# Status_LED.net
KiCad netlist of a schematic drawn in Altium Designer
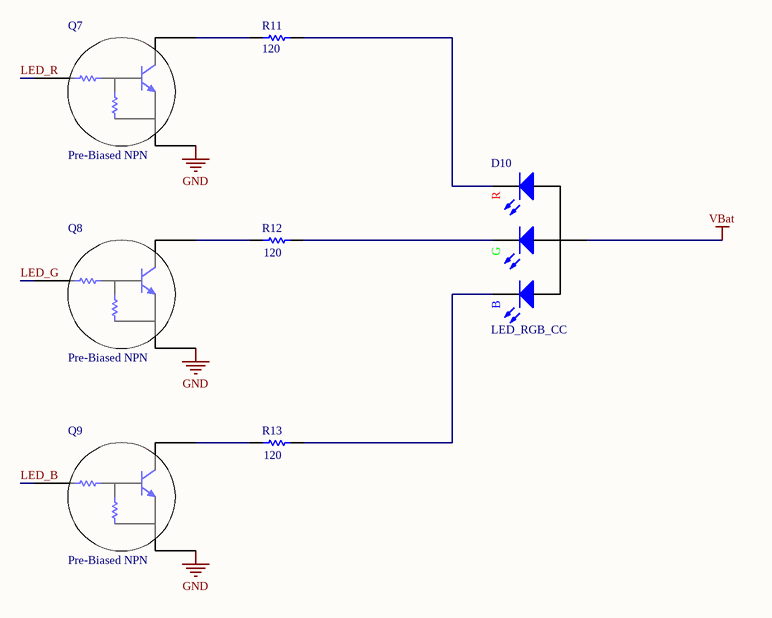
[diagram p0: Status_LED.SchDoc]

(export (version "E")
  (design (tool "Eeschema 10.0.6"))
  (components
    (comp (ref "D10")
      (value "LED_RGB_CC")
      (footprint "SM1210RGB")
      (description "RGB LED Common Cathode")
      (libsource (lib "passives") (part "LED_RGB_CC"))
    )
    (comp (ref "Q7")
      (value "Pre-Biased NPN")
      (footprint "SOT-416")
      (fields
        (field (name "MANUFACTURER PART NO") "DTD743EETL")
        (field (name "VENDOR PART NO") "DTD743EETLTR-ND")
      )
      (libsource (lib "transistors") (part "Pre-Biased NPN"))
    )
    (comp (ref "Q8")
      (value "Pre-Biased NPN")
      (footprint "SOT-416")
      (fields
        (field (name "MANUFACTURER PART NO") "DTD743EETL")
        (field (name "VENDOR PART NO") "DTD743EETLTR-ND")
      )
      (libsource (lib "transistors") (part "Pre-Biased NPN"))
    )
    (comp (ref "Q9")
      (value "Pre-Biased NPN")
      (footprint "SOT-416")
      (fields
        (field (name "MANUFACTURER PART NO") "DTD743EETL")
        (field (name "VENDOR PART NO") "DTD743EETLTR-ND")
      )
      (libsource (lib "transistors") (part "Pre-Biased NPN"))
    )
    (comp (ref "R11")
      (value "120")
      (footprint "0603")
      (description "Resistor")
      (fields (field (name "PUBLISHER") "Altium Limited"))
      (libsource (lib "passives") (part "Resistor"))
    )
    (comp (ref "R12")
      (value "120")
      (footprint "0603")
      (description "Resistor")
      (fields (field (name "PUBLISHER") "Altium Limited"))
      (libsource (lib "passives") (part "Resistor"))
    )
    (comp (ref "R13")
      (value "120")
      (footprint "0603")
      (description "Resistor")
      (fields (field (name "PUBLISHER") "Altium Limited"))
      (libsource (lib "passives") (part "Resistor"))
    )
  )
  (nets
    (net (code "1") (name "/LED_B") (class "Default")
      (node (ref "Q9") (pin "1") (pinfunction "1_1") (pintype "passive"))
    )
    (net (code "2") (name "/LED_G") (class "Default")
      (node (ref "Q8") (pin "1") (pinfunction "1_1") (pintype "passive"))
    )
    (net (code "3") (name "/LED_R") (class "Default")
      (node (ref "Q7") (pin "1") (pinfunction "1_1") (pintype "passive"))
    )
    (net (code "4") (name "GND") (class "Default")
      (node (ref "Q7") (pin "2") (pinfunction "2_2") (pintype "passive"))
      (node (ref "Q8") (pin "2") (pinfunction "2_2") (pintype "passive"))
      (node (ref "Q9") (pin "2") (pinfunction "2_2") (pintype "passive"))
    )
    (net (code "5") (name "Net-(D10-Pad2)") (class "Default")
      (node (ref "D10") (pin "2") (pinfunction "2_2") (pintype "passive"))
      (node (ref "R11") (pin "2") (pinfunction "2_2") (pintype "passive"))
    )
    (net (code "6") (name "Net-(D10-Pad3)") (class "Default")
      (node (ref "D10") (pin "3") (pinfunction "3_3") (pintype "passive"))
      (node (ref "R12") (pin "2") (pinfunction "2_2") (pintype "passive"))
    )
    (net (code "7") (name "Net-(D10-Pad4)") (class "Default")
      (node (ref "D10") (pin "4") (pinfunction "4_4") (pintype "passive"))
      (node (ref "R13") (pin "2") (pinfunction "2_2") (pintype "passive"))
    )
    (net (code "8") (name "Net-(Q7-Pad3)") (class "Default")
      (node (ref "Q7") (pin "3") (pinfunction "3_3") (pintype "passive"))
      (node (ref "R11") (pin "1") (pinfunction "1_1") (pintype "passive"))
    )
    (net (code "9") (name "Net-(Q8-Pad3)") (class "Default")
      (node (ref "Q8") (pin "3") (pinfunction "3_3") (pintype "passive"))
      (node (ref "R12") (pin "1") (pinfunction "1_1") (pintype "passive"))
    )
    (net (code "10") (name "Net-(Q9-Pad3)") (class "Default")
      (node (ref "Q9") (pin "3") (pinfunction "3_3") (pintype "passive"))
      (node (ref "R13") (pin "1") (pinfunction "1_1") (pintype "passive"))
    )
    (net (code "11") (name "VBat") (class "Default")
      (node (ref "D10") (pin "1") (pinfunction "1_1") (pintype "passive"))
    )
  )
)
